# DAC5672.net
KiCad netlist of a schematic drawn in Altium Designer
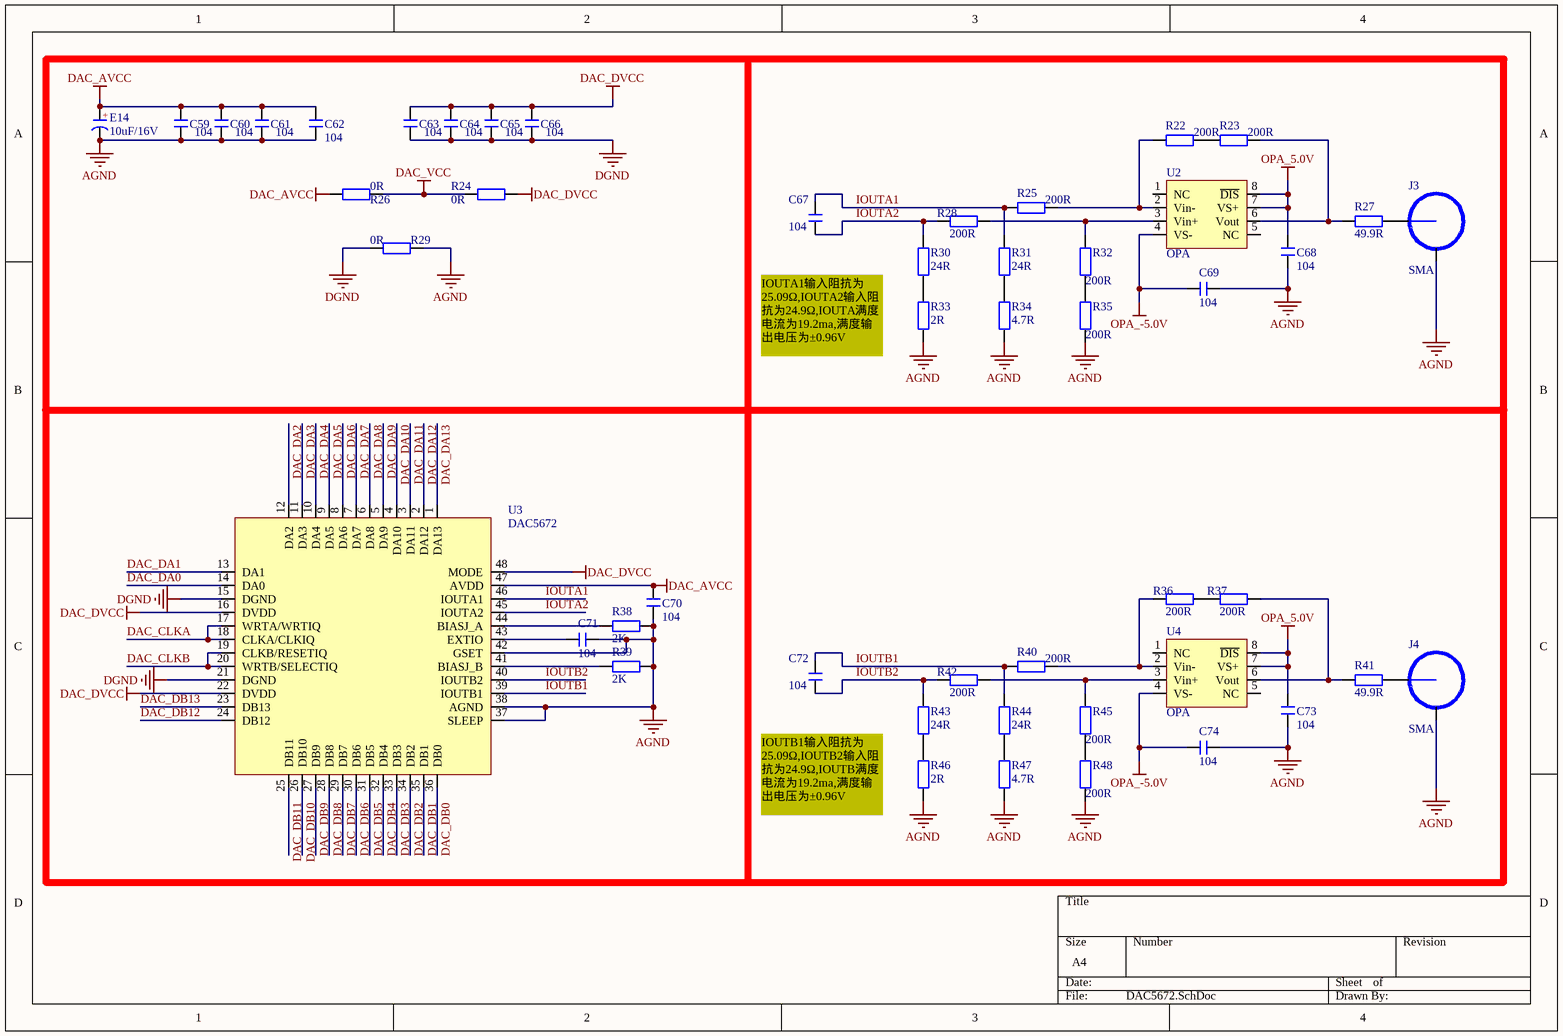
[diagram p0: DAC5672.SchDoc]

(export (version "E")
  (design (tool "Eeschema 10.0.6"))
  (components
    (comp (ref "C59")
      (value "104")
      (footprint "C 0805_M")
      (description "无极性贴片电容")
      (fields (field (name "版权归属") "源创客"))
      (libsource (lib "3.1   - 电阻-电容-电感") (part "C"))
    )
    (comp (ref "C60")
      (value "104")
      (footprint "C 0805_M")
      (description "无极性贴片电容")
      (fields (field (name "版权归属") "源创客"))
      (libsource (lib "3.1   - 电阻-电容-电感") (part "C"))
    )
    (comp (ref "C61")
      (value "104")
      (footprint "C 0805_M")
      (description "无极性贴片电容")
      (fields (field (name "版权归属") "源创客"))
      (libsource (lib "3.1   - 电阻-电容-电感") (part "C"))
    )
    (comp (ref "C62")
      (value "104")
      (footprint "C 0805_M")
      (description "无极性贴片电容")
      (fields (field (name "版权归属") "源创客"))
      (libsource (lib "3.1   - 电阻-电容-电感") (part "C"))
    )
    (comp (ref "C63")
      (value "104")
      (footprint "C 0805_M")
      (description "无极性贴片电容")
      (fields (field (name "版权归属") "源创客"))
      (libsource (lib "3.1   - 电阻-电容-电感") (part "C"))
    )
    (comp (ref "C64")
      (value "104")
      (footprint "C 0805_M")
      (description "无极性贴片电容")
      (fields (field (name "版权归属") "源创客"))
      (libsource (lib "3.1   - 电阻-电容-电感") (part "C"))
    )
    (comp (ref "C65")
      (value "104")
      (footprint "C 0805_M")
      (description "无极性贴片电容")
      (fields (field (name "版权归属") "源创客"))
      (libsource (lib "3.1   - 电阻-电容-电感") (part "C"))
    )
    (comp (ref "C66")
      (value "104")
      (footprint "C 0805_M")
      (description "无极性贴片电容")
      (fields (field (name "版权归属") "源创客"))
      (libsource (lib "3.1   - 电阻-电容-电感") (part "C"))
    )
    (comp (ref "C67")
      (value "104")
      (footprint "C 0805_M")
      (description "无极性贴片电容")
      (fields (field (name "版权归属") "源创客"))
      (libsource (lib "3.1   - 电阻-电容-电感") (part "C"))
    )
    (comp (ref "C68")
      (value "104")
      (footprint "C 0805_M")
      (description "无极性贴片电容")
      (fields (field (name "版权归属") "源创客"))
      (libsource (lib "3.1   - 电阻-电容-电感") (part "C"))
    )
    (comp (ref "C69")
      (value "104")
      (footprint "C 0805_M")
      (description "无极性贴片电容")
      (fields (field (name "版权归属") "源创客"))
      (libsource (lib "3.1   - 电阻-电容-电感") (part "C"))
    )
    (comp (ref "C70")
      (value "104")
      (footprint "C 0805_M")
      (description "无极性贴片电容")
      (fields (field (name "版权归属") "源创客"))
      (libsource (lib "3.1   - 电阻-电容-电感") (part "C"))
    )
    (comp (ref "C71")
      (value "104")
      (footprint "C 0805_M")
      (description "无极性贴片电容")
      (fields (field (name "版权归属") "源创客"))
      (libsource (lib "3.1   - 电阻-电容-电感") (part "C"))
    )
    (comp (ref "C72")
      (value "104")
      (footprint "C 0805_M")
      (description "无极性贴片电容")
      (fields (field (name "版权归属") "源创客"))
      (libsource (lib "3.1   - 电阻-电容-电感") (part "C"))
    )
    (comp (ref "C73")
      (value "104")
      (footprint "C 0805_M")
      (description "无极性贴片电容")
      (fields (field (name "版权归属") "源创客"))
      (libsource (lib "3.1   - 电阻-电容-电感") (part "C"))
    )
    (comp (ref "C74")
      (value "104")
      (footprint "C 0805_M")
      (description "无极性贴片电容")
      (fields (field (name "版权归属") "源创客"))
      (libsource (lib "3.1   - 电阻-电容-电感") (part "C"))
    )
    (comp (ref "E14")
      (value "10uF/16V")
      (footprint "C 1210_M")
      (description "直插电解电容")
      (fields (field (name "版权归属") "源创客"))
      (libsource (lib "3.1   - 电阻-电容-电感") (part "C-CAP"))
    )
    (comp (ref "J3") (value "SMA") (footprint "SMA_FR") (libsource (lib "电子竞赛") (part "SMA")))
    (comp (ref "J4") (value "SMA") (footprint "SMA_FR") (libsource (lib "电子竞赛") (part "SMA")))
    (comp (ref "R22")
      (value "200R")
      (footprint "R 0805_M")
      (description "贴片电阻")
      (fields (field (name "版权归属") "源创客"))
      (libsource (lib "3.1   - 电阻-电容-电感") (part "R"))
    )
    (comp (ref "R23")
      (value "200R")
      (footprint "R 0805_M")
      (description "贴片电阻")
      (fields (field (name "版权归属") "源创客"))
      (libsource (lib "3.1   - 电阻-电容-电感") (part "R"))
    )
    (comp (ref "R24")
      (value "0R")
      (footprint "R 0805_M")
      (description "贴片电阻")
      (fields (field (name "版权归属") "源创客"))
      (libsource (lib "3.1   - 电阻-电容-电感") (part "R"))
    )
    (comp (ref "R25")
      (value "200R")
      (footprint "R 0805_M")
      (description "贴片电阻")
      (fields (field (name "版权归属") "源创客"))
      (libsource (lib "3.1   - 电阻-电容-电感") (part "R"))
    )
    (comp (ref "R26")
      (value "0R")
      (footprint "R 0805_M")
      (description "贴片电阻")
      (fields (field (name "版权归属") "源创客"))
      (libsource (lib "3.1   - 电阻-电容-电感") (part "R"))
    )
    (comp (ref "R27")
      (value "49.9R")
      (footprint "R 0805_M")
      (description "贴片电阻")
      (fields (field (name "版权归属") "源创客"))
      (libsource (lib "3.1   - 电阻-电容-电感") (part "R"))
    )
    (comp (ref "R28")
      (value "200R")
      (footprint "R 0805_M")
      (description "贴片电阻")
      (fields (field (name "版权归属") "源创客"))
      (libsource (lib "3.1   - 电阻-电容-电感") (part "R"))
    )
    (comp (ref "R29")
      (value "0R")
      (footprint "R 1206_M")
      (description "贴片电阻")
      (fields (field (name "版权归属") "源创客"))
      (libsource (lib "3.1   - 电阻-电容-电感") (part "R"))
    )
    (comp (ref "R30")
      (value "24R")
      (footprint "R 0805_M")
      (description "贴片电阻")
      (fields (field (name "版权归属") "源创客"))
      (libsource (lib "3.1   - 电阻-电容-电感") (part "R"))
    )
    (comp (ref "R31")
      (value "24R")
      (footprint "R 0805_M")
      (description "贴片电阻")
      (fields (field (name "版权归属") "源创客"))
      (libsource (lib "3.1   - 电阻-电容-电感") (part "R"))
    )
    (comp (ref "R32")
      (value "200R")
      (footprint "R 0805_M")
      (description "贴片电阻")
      (fields (field (name "版权归属") "源创客"))
      (libsource (lib "3.1   - 电阻-电容-电感") (part "R"))
    )
    (comp (ref "R33")
      (value "2R")
      (footprint "R 0805_M")
      (description "贴片电阻")
      (fields (field (name "版权归属") "源创客"))
      (libsource (lib "3.1   - 电阻-电容-电感") (part "R"))
    )
    (comp (ref "R34")
      (value "4.7R")
      (footprint "R 0805_M")
      (description "贴片电阻")
      (fields (field (name "版权归属") "源创客"))
      (libsource (lib "3.1   - 电阻-电容-电感") (part "R"))
    )
    (comp (ref "R35")
      (value "200R")
      (footprint "R 0805_M")
      (description "贴片电阻")
      (fields (field (name "版权归属") "源创客"))
      (libsource (lib "3.1   - 电阻-电容-电感") (part "R"))
    )
    (comp (ref "R36")
      (value "200R")
      (footprint "R 0805_M")
      (description "贴片电阻")
      (fields (field (name "版权归属") "源创客"))
      (libsource (lib "3.1   - 电阻-电容-电感") (part "R"))
    )
    (comp (ref "R37")
      (value "200R")
      (footprint "R 0805_M")
      (description "贴片电阻")
      (fields (field (name "版权归属") "源创客"))
      (libsource (lib "3.1   - 电阻-电容-电感") (part "R"))
    )
    (comp (ref "R38")
      (value "2K")
      (footprint "R 0805_M")
      (description "贴片电阻")
      (fields (field (name "版权归属") "源创客"))
      (libsource (lib "3.1   - 电阻-电容-电感") (part "R"))
    )
    (comp (ref "R39")
      (value "2K")
      (footprint "R 0805_M")
      (description "贴片电阻")
      (fields (field (name "版权归属") "源创客"))
      (libsource (lib "3.1   - 电阻-电容-电感") (part "R"))
    )
    (comp (ref "R40")
      (value "200R")
      (footprint "R 0805_M")
      (description "贴片电阻")
      (fields (field (name "版权归属") "源创客"))
      (libsource (lib "3.1   - 电阻-电容-电感") (part "R"))
    )
    (comp (ref "R41")
      (value "49.9R")
      (footprint "R 0805_M")
      (description "贴片电阻")
      (fields (field (name "版权归属") "源创客"))
      (libsource (lib "3.1   - 电阻-电容-电感") (part "R"))
    )
    (comp (ref "R42")
      (value "200R")
      (footprint "R 0805_M")
      (description "贴片电阻")
      (fields (field (name "版权归属") "源创客"))
      (libsource (lib "3.1   - 电阻-电容-电感") (part "R"))
    )
    (comp (ref "R43")
      (value "24R")
      (footprint "R 0805_M")
      (description "贴片电阻")
      (fields (field (name "版权归属") "源创客"))
      (libsource (lib "3.1   - 电阻-电容-电感") (part "R"))
    )
    (comp (ref "R44")
      (value "24R")
      (footprint "R 0805_M")
      (description "贴片电阻")
      (fields (field (name "版权归属") "源创客"))
      (libsource (lib "3.1   - 电阻-电容-电感") (part "R"))
    )
    (comp (ref "R45")
      (value "200R")
      (footprint "R 0805_M")
      (description "贴片电阻")
      (fields (field (name "版权归属") "源创客"))
      (libsource (lib "3.1   - 电阻-电容-电感") (part "R"))
    )
    (comp (ref "R46")
      (value "2R")
      (footprint "R 0805_M")
      (description "贴片电阻")
      (fields (field (name "版权归属") "源创客"))
      (libsource (lib "3.1   - 电阻-电容-电感") (part "R"))
    )
    (comp (ref "R47")
      (value "4.7R")
      (footprint "R 0805_M")
      (description "贴片电阻")
      (fields (field (name "版权归属") "源创客"))
      (libsource (lib "3.1   - 电阻-电容-电感") (part "R"))
    )
    (comp (ref "R48")
      (value "200R")
      (footprint "R 0805_M")
      (description "贴片电阻")
      (fields (field (name "版权归属") "源创客"))
      (libsource (lib "3.1   - 电阻-电容-电感") (part "R"))
    )
    (comp (ref "U2") (value "OPA") (footprint "SOP8_M") (libsource (lib "电子竞赛") (part "单运放")))
    (comp (ref "U3") (value "DAC5672") (footprint "TQFP48 7x7_M") (libsource (lib "电子竞赛") (part "DAC5672")))
    (comp (ref "U4") (value "OPA") (footprint "SOP8_M") (libsource (lib "电子竞赛") (part "单运放")))
  )
  (nets
    (net (code "1") (name "/DAC_CLKA") (class "Default")
      (node (ref "U3") (pin "17") (pinfunction "WRTA/WRTIQ_17") (pintype "passive"))
      (node (ref "U3") (pin "18") (pinfunction "CLKA/CLKIQ_18") (pintype "passive"))
    )
    (net (code "2") (name "/DAC_CLKB") (class "Default")
      (node (ref "U3") (pin "19") (pinfunction "CLKB/RESETIQ_19") (pintype "passive"))
      (node (ref "U3") (pin "20") (pinfunction "WRTB/SELECTIQ_20") (pintype "passive"))
    )
    (net (code "3") (name "/DAC_DA0") (class "Default")
      (node (ref "U3") (pin "14") (pinfunction "DA0_14") (pintype "passive"))
    )
    (net (code "4") (name "/DAC_DA1") (class "Default")
      (node (ref "U3") (pin "13") (pinfunction "DA1_13") (pintype "passive"))
    )
    (net (code "5") (name "/DAC_DA2") (class "Default")
      (node (ref "U3") (pin "12") (pinfunction "DA2_12") (pintype "passive"))
    )
    (net (code "6") (name "/DAC_DA3") (class "Default")
      (node (ref "U3") (pin "11") (pinfunction "DA3_11") (pintype "passive"))
    )
    (net (code "7") (name "/DAC_DA4") (class "Default")
      (node (ref "U3") (pin "10") (pinfunction "DA4_10") (pintype "passive"))
    )
    (net (code "8") (name "/DAC_DA5") (class "Default")
      (node (ref "U3") (pin "9") (pinfunction "DA5_9") (pintype "passive"))
    )
    (net (code "9") (name "/DAC_DA6") (class "Default")
      (node (ref "U3") (pin "8") (pinfunction "DA6_8") (pintype "passive"))
    )
    (net (code "10") (name "/DAC_DA7") (class "Default")
      (node (ref "U3") (pin "7") (pinfunction "DA7_7") (pintype "passive"))
    )
    (net (code "11") (name "/DAC_DA8") (class "Default")
      (node (ref "U3") (pin "6") (pinfunction "DA8_6") (pintype "passive"))
    )
    (net (code "12") (name "/DAC_DA9") (class "Default")
      (node (ref "U3") (pin "5") (pinfunction "DA9_5") (pintype "passive"))
    )
    (net (code "13") (name "/DAC_DA10") (class "Default")
      (node (ref "U3") (pin "4") (pinfunction "DA10_4") (pintype "passive"))
    )
    (net (code "14") (name "/DAC_DA11") (class "Default")
      (node (ref "U3") (pin "3") (pinfunction "DA11_3") (pintype "passive"))
    )
    (net (code "15") (name "/DAC_DA12") (class "Default")
      (node (ref "U3") (pin "2") (pinfunction "DA12_2") (pintype "passive"))
    )
    (net (code "16") (name "/DAC_DA13") (class "Default")
      (node (ref "U3") (pin "1") (pinfunction "DA13_1") (pintype "passive"))
    )
    (net (code "17") (name "/DAC_DB0") (class "Default")
      (node (ref "U3") (pin "36") (pinfunction "DB0_36") (pintype "passive"))
    )
    (net (code "18") (name "/DAC_DB1") (class "Default")
      (node (ref "U3") (pin "35") (pinfunction "DB1_35") (pintype "passive"))
    )
    (net (code "19") (name "/DAC_DB2") (class "Default")
      (node (ref "U3") (pin "34") (pinfunction "DB2_34") (pintype "passive"))
    )
    (net (code "20") (name "/DAC_DB3") (class "Default")
      (node (ref "U3") (pin "33") (pinfunction "DB3_33") (pintype "passive"))
    )
    (net (code "21") (name "/DAC_DB4") (class "Default")
      (node (ref "U3") (pin "32") (pinfunction "DB4_32") (pintype "passive"))
    )
    (net (code "22") (name "/DAC_DB5") (class "Default")
      (node (ref "U3") (pin "31") (pinfunction "DB5_31") (pintype "passive"))
    )
    (net (code "23") (name "/DAC_DB6") (class "Default")
      (node (ref "U3") (pin "30") (pinfunction "DB6_30") (pintype "passive"))
    )
    (net (code "24") (name "/DAC_DB7") (class "Default")
      (node (ref "U3") (pin "29") (pinfunction "DB7_29") (pintype "passive"))
    )
    (net (code "25") (name "/DAC_DB8") (class "Default")
      (node (ref "U3") (pin "28") (pinfunction "DB8_28") (pintype "passive"))
    )
    (net (code "26") (name "/DAC_DB9") (class "Default")
      (node (ref "U3") (pin "27") (pinfunction "DB9_27") (pintype "passive"))
    )
    (net (code "27") (name "/DAC_DB10") (class "Default")
      (node (ref "U3") (pin "26") (pinfunction "DB10_26") (pintype "passive"))
    )
    (net (code "28") (name "/DAC_DB11") (class "Default")
      (node (ref "U3") (pin "25") (pinfunction "DB11_25") (pintype "passive"))
    )
    (net (code "29") (name "/DAC_DB12") (class "Default")
      (node (ref "U3") (pin "24") (pinfunction "DB12_24") (pintype "passive"))
    )
    (net (code "30") (name "/DAC_DB13") (class "Default")
      (node (ref "U3") (pin "23") (pinfunction "DB13_23") (pintype "passive"))
    )
    (net (code "31") (name "/IOUTA1") (class "Default")
      (node (ref "C67") (pin "1") (pinfunction "1_1") (pintype "passive"))
      (node (ref "R25") (pin "2") (pinfunction "2_2") (pintype "passive"))
      (node (ref "R31") (pin "1") (pinfunction "1_1") (pintype "passive"))
      (node (ref "U3") (pin "46") (pinfunction "IOUTA1_46") (pintype "passive"))
    )
    (net (code "32") (name "/IOUTA2") (class "Default")
      (node (ref "C67") (pin "2") (pinfunction "2_2") (pintype "passive"))
      (node (ref "R28") (pin "2") (pinfunction "2_2") (pintype "passive"))
      (node (ref "R30") (pin "2") (pinfunction "2_2") (pintype "passive"))
      (node (ref "U3") (pin "45") (pinfunction "IOUTA2_45") (pintype "passive"))
    )
    (net (code "33") (name "/IOUTB1") (class "Default")
      (node (ref "C72") (pin "1") (pinfunction "1_1") (pintype "passive"))
      (node (ref "R40") (pin "2") (pinfunction "2_2") (pintype "passive"))
      (node (ref "R44") (pin "1") (pinfunction "1_1") (pintype "passive"))
      (node (ref "U3") (pin "39") (pinfunction "IOUTB1_39") (pintype "passive"))
    )
    (net (code "34") (name "/IOUTB2") (class "Default")
      (node (ref "C72") (pin "2") (pinfunction "2_2") (pintype "passive"))
      (node (ref "R42") (pin "2") (pinfunction "2_2") (pintype "passive"))
      (node (ref "R43") (pin "2") (pinfunction "2_2") (pintype "passive"))
      (node (ref "U3") (pin "40") (pinfunction "IOUTB2_40") (pintype "passive"))
    )
    (net (code "35") (name "AGND") (class "Default")
      (node (ref "C59") (pin "1") (pinfunction "1_1") (pintype "passive"))
      (node (ref "C60") (pin "1") (pinfunction "1_1") (pintype "passive"))
      (node (ref "C61") (pin "1") (pinfunction "1_1") (pintype "passive"))
      (node (ref "C62") (pin "1") (pinfunction "1_1") (pintype "passive"))
      (node (ref "C68") (pin "1") (pinfunction "1_1") (pintype "passive"))
      (node (ref "C69") (pin "1") (pinfunction "1_1") (pintype "passive"))
      (node (ref "C70") (pin "1") (pinfunction "1_1") (pintype "passive"))
      (node (ref "C71") (pin "2") (pinfunction "2_2") (pintype "passive"))
      (node (ref "C73") (pin "1") (pinfunction "1_1") (pintype "passive"))
      (node (ref "C74") (pin "1") (pinfunction "1_1") (pintype "passive"))
      (node (ref "E14") (pin "2") (pinfunction "K_2") (pintype "passive"))
      (node (ref "J3") (pin "2") (pinfunction "2_2") (pintype "passive"))
      (node (ref "J4") (pin "2") (pinfunction "2_2") (pintype "passive"))
      (node (ref "R29") (pin "2") (pinfunction "2_2") (pintype "passive"))
      (node (ref "R33") (pin "1") (pinfunction "1_1") (pintype "passive"))
      (node (ref "R34") (pin "2") (pinfunction "2_2") (pintype "passive"))
      (node (ref "R35") (pin "2") (pinfunction "2_2") (pintype "passive"))
      (node (ref "R38") (pin "2") (pinfunction "2_2") (pintype "passive"))
      (node (ref "R39") (pin "2") (pinfunction "2_2") (pintype "passive"))
      (node (ref "R46") (pin "1") (pinfunction "1_1") (pintype "passive"))
      (node (ref "R47") (pin "2") (pinfunction "2_2") (pintype "passive"))
      (node (ref "R48") (pin "2") (pinfunction "2_2") (pintype "passive"))
      (node (ref "U3") (pin "37") (pinfunction "SLEEP_37") (pintype "passive"))
      (node (ref "U3") (pin "38") (pinfunction "AGND_38") (pintype "passive"))
      (node (ref "U3") (pin "42") (pinfunction "GSET_42") (pintype "passive"))
    )
    (net (code "36") (name "DAC_AVCC") (class "Default")
      (node (ref "C59") (pin "2") (pinfunction "2_2") (pintype "passive"))
      (node (ref "C60") (pin "2") (pinfunction "2_2") (pintype "passive"))
      (node (ref "C61") (pin "2") (pinfunction "2_2") (pintype "passive"))
      (node (ref "C62") (pin "2") (pinfunction "2_2") (pintype "passive"))
      (node (ref "C70") (pin "2") (pinfunction "2_2") (pintype "passive"))
      (node (ref "E14") (pin "1") (pinfunction "A_1") (pintype "passive"))
      (node (ref "R26") (pin "1") (pinfunction "1_1") (pintype "passive"))
      (node (ref "U3") (pin "47") (pinfunction "AVDD_47") (pintype "passive"))
    )
    (net (code "37") (name "DAC_DVCC") (class "Default")
      (node (ref "C63") (pin "2") (pinfunction "2_2") (pintype "passive"))
      (node (ref "C64") (pin "2") (pinfunction "2_2") (pintype "passive"))
      (node (ref "C65") (pin "2") (pinfunction "2_2") (pintype "passive"))
      (node (ref "C66") (pin "2") (pinfunction "2_2") (pintype "passive"))
      (node (ref "R24") (pin "2") (pinfunction "2_2") (pintype "passive"))
      (node (ref "U3") (pin "16") (pinfunction "DVDD_16") (pintype "passive"))
      (node (ref "U3") (pin "22") (pinfunction "DVDD_22") (pintype "passive"))
      (node (ref "U3") (pin "48") (pinfunction "MODE_48") (pintype "passive"))
    )
    (net (code "38") (name "DAC_VCC") (class "Default")
      (node (ref "R24") (pin "1") (pinfunction "1_1") (pintype "passive"))
      (node (ref "R26") (pin "2") (pinfunction "2_2") (pintype "passive"))
    )
    (net (code "39") (name "DGND") (class "Default")
      (node (ref "C63") (pin "1") (pinfunction "1_1") (pintype "passive"))
      (node (ref "C64") (pin "1") (pinfunction "1_1") (pintype "passive"))
      (node (ref "C65") (pin "1") (pinfunction "1_1") (pintype "passive"))
      (node (ref "C66") (pin "1") (pinfunction "1_1") (pintype "passive"))
      (node (ref "R29") (pin "1") (pinfunction "1_1") (pintype "passive"))
      (node (ref "U3") (pin "15") (pinfunction "DGND_15") (pintype "passive"))
      (node (ref "U3") (pin "21") (pinfunction "DGND_21") (pintype "passive"))
    )
    (net (code "40") (name "Net-(J3-Pad1)") (class "Default")
      (node (ref "J3") (pin "1") (pinfunction "1_1") (pintype "passive"))
      (node (ref "R27") (pin "2") (pinfunction "2_2") (pintype "passive"))
    )
    (net (code "41") (name "Net-(J4-Pad1)") (class "Default")
      (node (ref "J4") (pin "1") (pinfunction "1_1") (pintype "passive"))
      (node (ref "R41") (pin "2") (pinfunction "2_2") (pintype "passive"))
    )
    (net (code "42") (name "Net-(R22-Pad1)") (class "Default")
      (node (ref "R22") (pin "1") (pinfunction "1_1") (pintype "passive"))
      (node (ref "R23") (pin "2") (pinfunction "2_2") (pintype "passive"))
    )
    (net (code "43") (name "Net-(R30-Pad1)") (class "Default")
      (node (ref "R30") (pin "1") (pinfunction "1_1") (pintype "passive"))
      (node (ref "R33") (pin "2") (pinfunction "2_2") (pintype "passive"))
    )
    (net (code "44") (name "Net-(R31-Pad2)") (class "Default")
      (node (ref "R31") (pin "2") (pinfunction "2_2") (pintype "passive"))
      (node (ref "R34") (pin "1") (pinfunction "1_1") (pintype "passive"))
    )
    (net (code "45") (name "Net-(R32-Pad2)") (class "Default")
      (node (ref "R32") (pin "2") (pinfunction "2_2") (pintype "passive"))
      (node (ref "R35") (pin "1") (pinfunction "1_1") (pintype "passive"))
    )
    (net (code "46") (name "Net-(R36-Pad1)") (class "Default")
      (node (ref "R36") (pin "1") (pinfunction "1_1") (pintype "passive"))
      (node (ref "R37") (pin "2") (pinfunction "2_2") (pintype "passive"))
    )
    (net (code "47") (name "Net-(R43-Pad1)") (class "Default")
      (node (ref "R43") (pin "1") (pinfunction "1_1") (pintype "passive"))
      (node (ref "R46") (pin "2") (pinfunction "2_2") (pintype "passive"))
    )
    (net (code "48") (name "Net-(R44-Pad2)") (class "Default")
      (node (ref "R44") (pin "2") (pinfunction "2_2") (pintype "passive"))
      (node (ref "R47") (pin "1") (pinfunction "1_1") (pintype "passive"))
    )
    (net (code "49") (name "Net-(R45-Pad1)") (class "Default")
      (node (ref "R45") (pin "1") (pinfunction "1_1") (pintype "passive"))
      (node (ref "R48") (pin "1") (pinfunction "1_1") (pintype "passive"))
    )
    (net (code "50") (name "Net-(U2-Vin+)") (class "Default")
      (node (ref "R28") (pin "1") (pinfunction "1_1") (pintype "passive"))
      (node (ref "R32") (pin "1") (pinfunction "1_1") (pintype "passive"))
      (node (ref "U2") (pin "3") (pinfunction "Vin+_3") (pintype "passive"))
    )
    (net (code "51") (name "Net-(U2-Vin-)") (class "Default")
      (node (ref "R22") (pin "2") (pinfunction "2_2") (pintype "passive"))
      (node (ref "R25") (pin "1") (pinfunction "1_1") (pintype "passive"))
      (node (ref "U2") (pin "2") (pinfunction "Vin-_2") (pintype "passive"))
    )
    (net (code "52") (name "Net-(U2-Vout)") (class "Default")
      (node (ref "R23") (pin "1") (pinfunction "1_1") (pintype "passive"))
      (node (ref "R27") (pin "1") (pinfunction "1_1") (pintype "passive"))
      (node (ref "U2") (pin "6") (pinfunction "Vout_6") (pintype "passive"))
    )
    (net (code "53") (name "Net-(U3-BIASJ_A)") (class "Default")
      (node (ref "R38") (pin "1") (pinfunction "1_1") (pintype "passive"))
      (node (ref "U3") (pin "44") (pinfunction "BIASJ_A_44") (pintype "passive"))
    )
    (net (code "54") (name "Net-(U3-BIASJ_B)") (class "Default")
      (node (ref "R39") (pin "1") (pinfunction "1_1") (pintype "passive"))
      (node (ref "U3") (pin "41") (pinfunction "BIASJ_B_41") (pintype "passive"))
    )
    (net (code "55") (name "Net-(U3-EXTIO)") (class "Default")
      (node (ref "C71") (pin "1") (pinfunction "1_1") (pintype "passive"))
      (node (ref "U3") (pin "43") (pinfunction "EXTIO_43") (pintype "passive"))
    )
    (net (code "56") (name "Net-(U4-Vin+)") (class "Default")
      (node (ref "R42") (pin "1") (pinfunction "1_1") (pintype "passive"))
      (node (ref "R45") (pin "2") (pinfunction "2_2") (pintype "passive"))
      (node (ref "U4") (pin "3") (pinfunction "Vin+_3") (pintype "passive"))
    )
    (net (code "57") (name "Net-(U4-Vin-)") (class "Default")
      (node (ref "R36") (pin "2") (pinfunction "2_2") (pintype "passive"))
      (node (ref "R40") (pin "1") (pinfunction "1_1") (pintype "passive"))
      (node (ref "U4") (pin "2") (pinfunction "Vin-_2") (pintype "passive"))
    )
    (net (code "58") (name "Net-(U4-Vout)") (class "Default")
      (node (ref "R37") (pin "1") (pinfunction "1_1") (pintype "passive"))
      (node (ref "R41") (pin "1") (pinfunction "1_1") (pintype "passive"))
      (node (ref "U4") (pin "6") (pinfunction "Vout_6") (pintype "passive"))
    )
    (net (code "59") (name "OPA_-5.0V") (class "Default")
      (node (ref "C69") (pin "2") (pinfunction "2_2") (pintype "passive"))
      (node (ref "C74") (pin "2") (pinfunction "2_2") (pintype "passive"))
      (node (ref "U2") (pin "4") (pinfunction "VS-_4") (pintype "passive"))
      (node (ref "U4") (pin "4") (pinfunction "VS-_4") (pintype "passive"))
    )
    (net (code "60") (name "OPA_5.0V") (class "Default")
      (node (ref "C68") (pin "2") (pinfunction "2_2") (pintype "passive"))
      (node (ref "C73") (pin "2") (pinfunction "2_2") (pintype "passive"))
      (node (ref "U2") (pin "7") (pinfunction "VS+_7") (pintype "passive"))
      (node (ref "U2") (pin "8") (pinfunction "~{DIS}_8") (pintype "passive"))
      (node (ref "U4") (pin "7") (pinfunction "VS+_7") (pintype "passive"))
      (node (ref "U4") (pin "8") (pinfunction "~{DIS}_8") (pintype "passive"))
    )
    (net (code "61") (name "unconnected-(U2-NC-Pad1)") (class "Default")
      (node (ref "U2") (pin "1") (pinfunction "NC_1") (pintype "passive"))
    )
    (net (code "62") (name "unconnected-(U2-NC-Pad5)") (class "Default")
      (node (ref "U2") (pin "5") (pinfunction "NC_5") (pintype "passive"))
    )
    (net (code "63") (name "unconnected-(U4-NC-Pad1)") (class "Default")
      (node (ref "U4") (pin "1") (pinfunction "NC_1") (pintype "passive"))
    )
    (net (code "64") (name "unconnected-(U4-NC-Pad5)") (class "Default")
      (node (ref "U4") (pin "5") (pinfunction "NC_5") (pintype "passive"))
    )
  )
)
